# UsbC.net
KiCad netlist of a schematic drawn in EAGLE
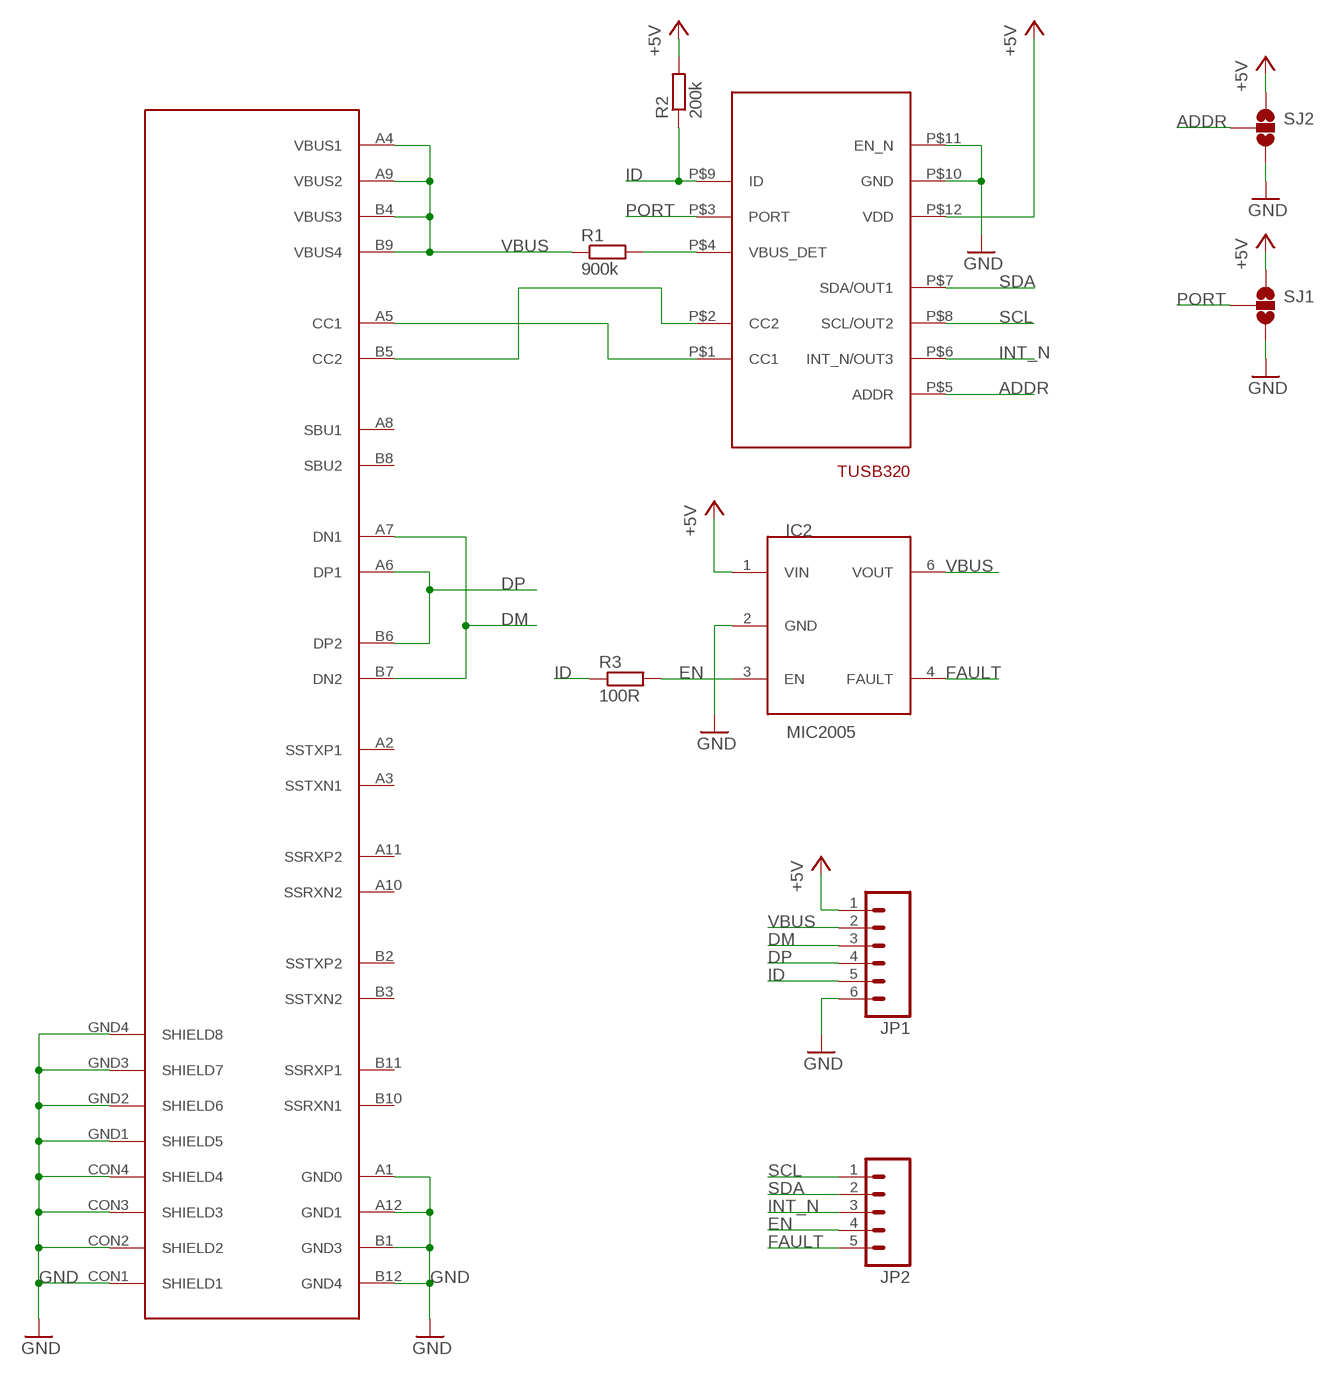
[diagram p0: schematic, sheet 1]

(export (version "E")
  (design (tool "Eeschema 10.0.6"))
  (components
    (comp (ref "CONN1")
      (value "USB-C_WURTH_632723X00011USB-C")
      (footprint "eagle-import:USB-C_WURTH_632723X00011")
      (libsource (lib "eagle-import") (part "USB-C_WURTH_632723X00011USB-C"))
    )
    (comp (ref "IC1")
      (value "TUSB320XQFN")
      (footprint "eagle-import:X2QFN")
      (libsource (lib "eagle-import") (part "TUSB320XQFN"))
    )
    (comp (ref "IC2")
      (value "MIC2005")
      (footprint "eagle-import:SOT23-6")
      (libsource (lib "eagle-import") (part "MIC2005"))
    )
    (comp (ref "JP1")
      (value "M06SIP")
      (footprint "eagle-import:1X06")
      (libsource (lib "eagle-import") (part "M06SIP"))
    )
    (comp (ref "JP2")
      (value "M05PTH")
      (footprint "eagle-import:1X05")
      (libsource (lib "eagle-import") (part "M05PTH"))
    )
    (comp (ref "R1")
      (value "900k")
      (footprint "eagle-import:0603")
      (libsource (lib "eagle-import") (part "R-EU_0603"))
    )
    (comp (ref "R2")
      (value "200k")
      (footprint "eagle-import:0603")
      (libsource (lib "eagle-import") (part "R-EU_0603"))
    )
    (comp (ref "R3")
      (value "100R")
      (footprint "eagle-import:0603")
      (libsource (lib "eagle-import") (part "R-EU_0603"))
    )
    (comp (ref "SJ1")
      (value "SOLDERJUMPER_2WAYS")
      (footprint "eagle-import:SJ_3")
      (libsource (lib "eagle-import") (part "SOLDERJUMPER_2WAYS"))
    )
    (comp (ref "SJ2")
      (value "SOLDERJUMPER_2WAYS")
      (footprint "eagle-import:SJ_3")
      (libsource (lib "eagle-import") (part "SOLDERJUMPER_2WAYS"))
    )
  )
  (nets
    (net (code "1") (name "+5V") (class "Default")
      (node (ref "IC1") (pin "P$12") (pinfunction "VDD_P$12") (pintype "bidirectional"))
      (node (ref "IC2") (pin "1") (pinfunction "VIN_1") (pintype "power_in"))
      (node (ref "JP1") (pin "1") (pinfunction "1_1") (pintype "passive"))
      (node (ref "R2") (pin "2") (pinfunction "2_2") (pintype "passive"))
      (node (ref "SJ1") (pin "1") (pinfunction "1_1") (pintype "passive"))
      (node (ref "SJ2") (pin "1") (pinfunction "1_1") (pintype "passive"))
    )
    (net (code "2") (name "/ADDR") (class "Default")
      (node (ref "IC1") (pin "P$5") (pinfunction "ADDR_P$5") (pintype "bidirectional"))
      (node (ref "SJ2") (pin "2") (pinfunction "2_2") (pintype "passive"))
    )
    (net (code "3") (name "/DM") (class "Default")
      (node (ref "CONN1") (pin "A7") (pinfunction "DN1_A7") (pintype "bidirectional"))
      (node (ref "CONN1") (pin "B7") (pinfunction "DN2_B7") (pintype "bidirectional"))
      (node (ref "JP1") (pin "3") (pinfunction "3_3") (pintype "passive"))
    )
    (net (code "4") (name "/DP") (class "Default")
      (node (ref "CONN1") (pin "A6") (pinfunction "DP1_A6") (pintype "bidirectional"))
      (node (ref "CONN1") (pin "B6") (pinfunction "DP2_B6") (pintype "bidirectional"))
      (node (ref "JP1") (pin "4") (pinfunction "4_4") (pintype "passive"))
    )
    (net (code "5") (name "/EN") (class "Default")
      (node (ref "IC2") (pin "3") (pinfunction "EN_3") (pintype "input"))
      (node (ref "JP2") (pin "4") (pinfunction "4_4") (pintype "passive"))
      (node (ref "R3") (pin "2") (pinfunction "2_2") (pintype "passive"))
    )
    (net (code "6") (name "/FAULT") (class "Default")
      (node (ref "IC2") (pin "4") (pinfunction "FAULT_4") (pintype "output"))
      (node (ref "JP2") (pin "5") (pinfunction "5_5") (pintype "passive"))
    )
    (net (code "7") (name "/ID") (class "Default")
      (node (ref "IC1") (pin "P$9") (pinfunction "ID_P$9") (pintype "bidirectional"))
      (node (ref "JP1") (pin "5") (pinfunction "5_5") (pintype "passive"))
      (node (ref "R2") (pin "1") (pinfunction "1_1") (pintype "passive"))
      (node (ref "R3") (pin "1") (pinfunction "1_1") (pintype "passive"))
    )
    (net (code "8") (name "/INT_N") (class "Default")
      (node (ref "IC1") (pin "P$6") (pinfunction "INT_N/OUT3_P$6") (pintype "bidirectional"))
      (node (ref "JP2") (pin "3") (pinfunction "3_3") (pintype "passive"))
    )
    (net (code "9") (name "/PORT") (class "Default")
      (node (ref "IC1") (pin "P$3") (pinfunction "PORT_P$3") (pintype "bidirectional"))
      (node (ref "SJ1") (pin "2") (pinfunction "2_2") (pintype "passive"))
    )
    (net (code "10") (name "/SCL") (class "Default")
      (node (ref "IC1") (pin "P$8") (pinfunction "SCL/OUT2_P$8") (pintype "bidirectional"))
      (node (ref "JP2") (pin "1") (pinfunction "1_1") (pintype "passive"))
    )
    (net (code "11") (name "/SDA") (class "Default")
      (node (ref "IC1") (pin "P$7") (pinfunction "SDA/OUT1_P$7") (pintype "bidirectional"))
      (node (ref "JP2") (pin "2") (pinfunction "2_2") (pintype "passive"))
    )
    (net (code "12") (name "/VBUS") (class "Default")
      (node (ref "CONN1") (pin "A4") (pinfunction "VBUS1_A4") (pintype "bidirectional"))
      (node (ref "CONN1") (pin "A9") (pinfunction "VBUS2_A9") (pintype "bidirectional"))
      (node (ref "CONN1") (pin "B4") (pinfunction "VBUS3_B4") (pintype "bidirectional"))
      (node (ref "CONN1") (pin "B9") (pinfunction "VBUS4_B9") (pintype "bidirectional"))
      (node (ref "IC2") (pin "6") (pinfunction "VOUT_6") (pintype "output"))
      (node (ref "JP1") (pin "2") (pinfunction "2_2") (pintype "passive"))
      (node (ref "R1") (pin "1") (pinfunction "1_1") (pintype "passive"))
    )
    (net (code "13") (name "GND") (class "Default")
      (node (ref "CONN1") (pin "A1") (pinfunction "GND0_A1") (pintype "bidirectional"))
      (node (ref "CONN1") (pin "A12") (pinfunction "GND1_A12") (pintype "bidirectional"))
      (node (ref "CONN1") (pin "B1") (pinfunction "GND3_B1") (pintype "bidirectional"))
      (node (ref "CONN1") (pin "B12") (pinfunction "GND4_B12") (pintype "bidirectional"))
      (node (ref "CONN1") (pin "CON1") (pinfunction "SHIELD1_CON1") (pintype "bidirectional"))
      (node (ref "CONN1") (pin "CON2") (pinfunction "SHIELD2_CON2") (pintype "bidirectional"))
      (node (ref "CONN1") (pin "CON3") (pinfunction "SHIELD3_CON3") (pintype "bidirectional"))
      (node (ref "CONN1") (pin "CON4") (pinfunction "SHIELD4_CON4") (pintype "bidirectional"))
      (node (ref "CONN1") (pin "GND1") (pinfunction "SHIELD5_GND1") (pintype "bidirectional"))
      (node (ref "CONN1") (pin "GND2") (pinfunction "SHIELD6_GND2") (pintype "bidirectional"))
      (node (ref "CONN1") (pin "GND3") (pinfunction "SHIELD7_GND3") (pintype "bidirectional"))
      (node (ref "CONN1") (pin "GND4") (pinfunction "SHIELD8_GND4") (pintype "bidirectional"))
      (node (ref "IC1") (pin "P$10") (pinfunction "GND_P$10") (pintype "bidirectional"))
      (node (ref "IC1") (pin "P$11") (pinfunction "EN_N_P$11") (pintype "bidirectional"))
      (node (ref "IC2") (pin "2") (pinfunction "GND_2") (pintype "power_in"))
      (node (ref "JP1") (pin "6") (pinfunction "6_6") (pintype "passive"))
      (node (ref "SJ1") (pin "3") (pinfunction "3_3") (pintype "passive"))
      (node (ref "SJ2") (pin "3") (pinfunction "3_3") (pintype "passive"))
    )
    (net (code "14") (name "Net-(CONN1-CC1)") (class "Default")
      (node (ref "CONN1") (pin "A5") (pinfunction "CC1_A5") (pintype "bidirectional"))
      (node (ref "IC1") (pin "P$1") (pinfunction "CC1_P$1") (pintype "bidirectional"))
    )
    (net (code "15") (name "Net-(CONN1-CC2)") (class "Default")
      (node (ref "CONN1") (pin "B5") (pinfunction "CC2_B5") (pintype "bidirectional"))
      (node (ref "IC1") (pin "P$2") (pinfunction "CC2_P$2") (pintype "bidirectional"))
    )
    (net (code "16") (name "Net-(IC1-VBUS_DET)") (class "Default")
      (node (ref "IC1") (pin "P$4") (pinfunction "VBUS_DET_P$4") (pintype "bidirectional"))
      (node (ref "R1") (pin "2") (pinfunction "2_2") (pintype "passive"))
    )
    (net (code "17") (name "unconnected-(CONN1-SBU1-PadA8)") (class "Default")
      (node (ref "CONN1") (pin "A8") (pinfunction "SBU1_A8") (pintype "bidirectional"))
    )
    (net (code "18") (name "unconnected-(CONN1-SBU2-PadB8)") (class "Default")
      (node (ref "CONN1") (pin "B8") (pinfunction "SBU2_B8") (pintype "bidirectional"))
    )
    (net (code "19") (name "unconnected-(CONN1-SSRXN1-PadB10)") (class "Default")
      (node (ref "CONN1") (pin "B10") (pinfunction "SSRXN1_B10") (pintype "bidirectional"))
    )
    (net (code "20") (name "unconnected-(CONN1-SSRXN2-PadA10)") (class "Default")
      (node (ref "CONN1") (pin "A10") (pinfunction "SSRXN2_A10") (pintype "bidirectional"))
    )
    (net (code "21") (name "unconnected-(CONN1-SSRXP1-PadB11)") (class "Default")
      (node (ref "CONN1") (pin "B11") (pinfunction "SSRXP1_B11") (pintype "bidirectional"))
    )
    (net (code "22") (name "unconnected-(CONN1-SSRXP2-PadA11)") (class "Default")
      (node (ref "CONN1") (pin "A11") (pinfunction "SSRXP2_A11") (pintype "bidirectional"))
    )
    (net (code "23") (name "unconnected-(CONN1-SSTXN1-PadA3)") (class "Default")
      (node (ref "CONN1") (pin "A3") (pinfunction "SSTXN1_A3") (pintype "bidirectional"))
    )
    (net (code "24") (name "unconnected-(CONN1-SSTXN2-PadB3)") (class "Default")
      (node (ref "CONN1") (pin "B3") (pinfunction "SSTXN2_B3") (pintype "bidirectional"))
    )
    (net (code "25") (name "unconnected-(CONN1-SSTXP1-PadA2)") (class "Default")
      (node (ref "CONN1") (pin "A2") (pinfunction "SSTXP1_A2") (pintype "bidirectional"))
    )
    (net (code "26") (name "unconnected-(CONN1-SSTXP2-PadB2)") (class "Default")
      (node (ref "CONN1") (pin "B2") (pinfunction "SSTXP2_B2") (pintype "bidirectional"))
    )
  )
)
